# full_hand_circuit_esp_v7_1_no_butt.net
KiCad netlist of a schematic drawn in EAGLE
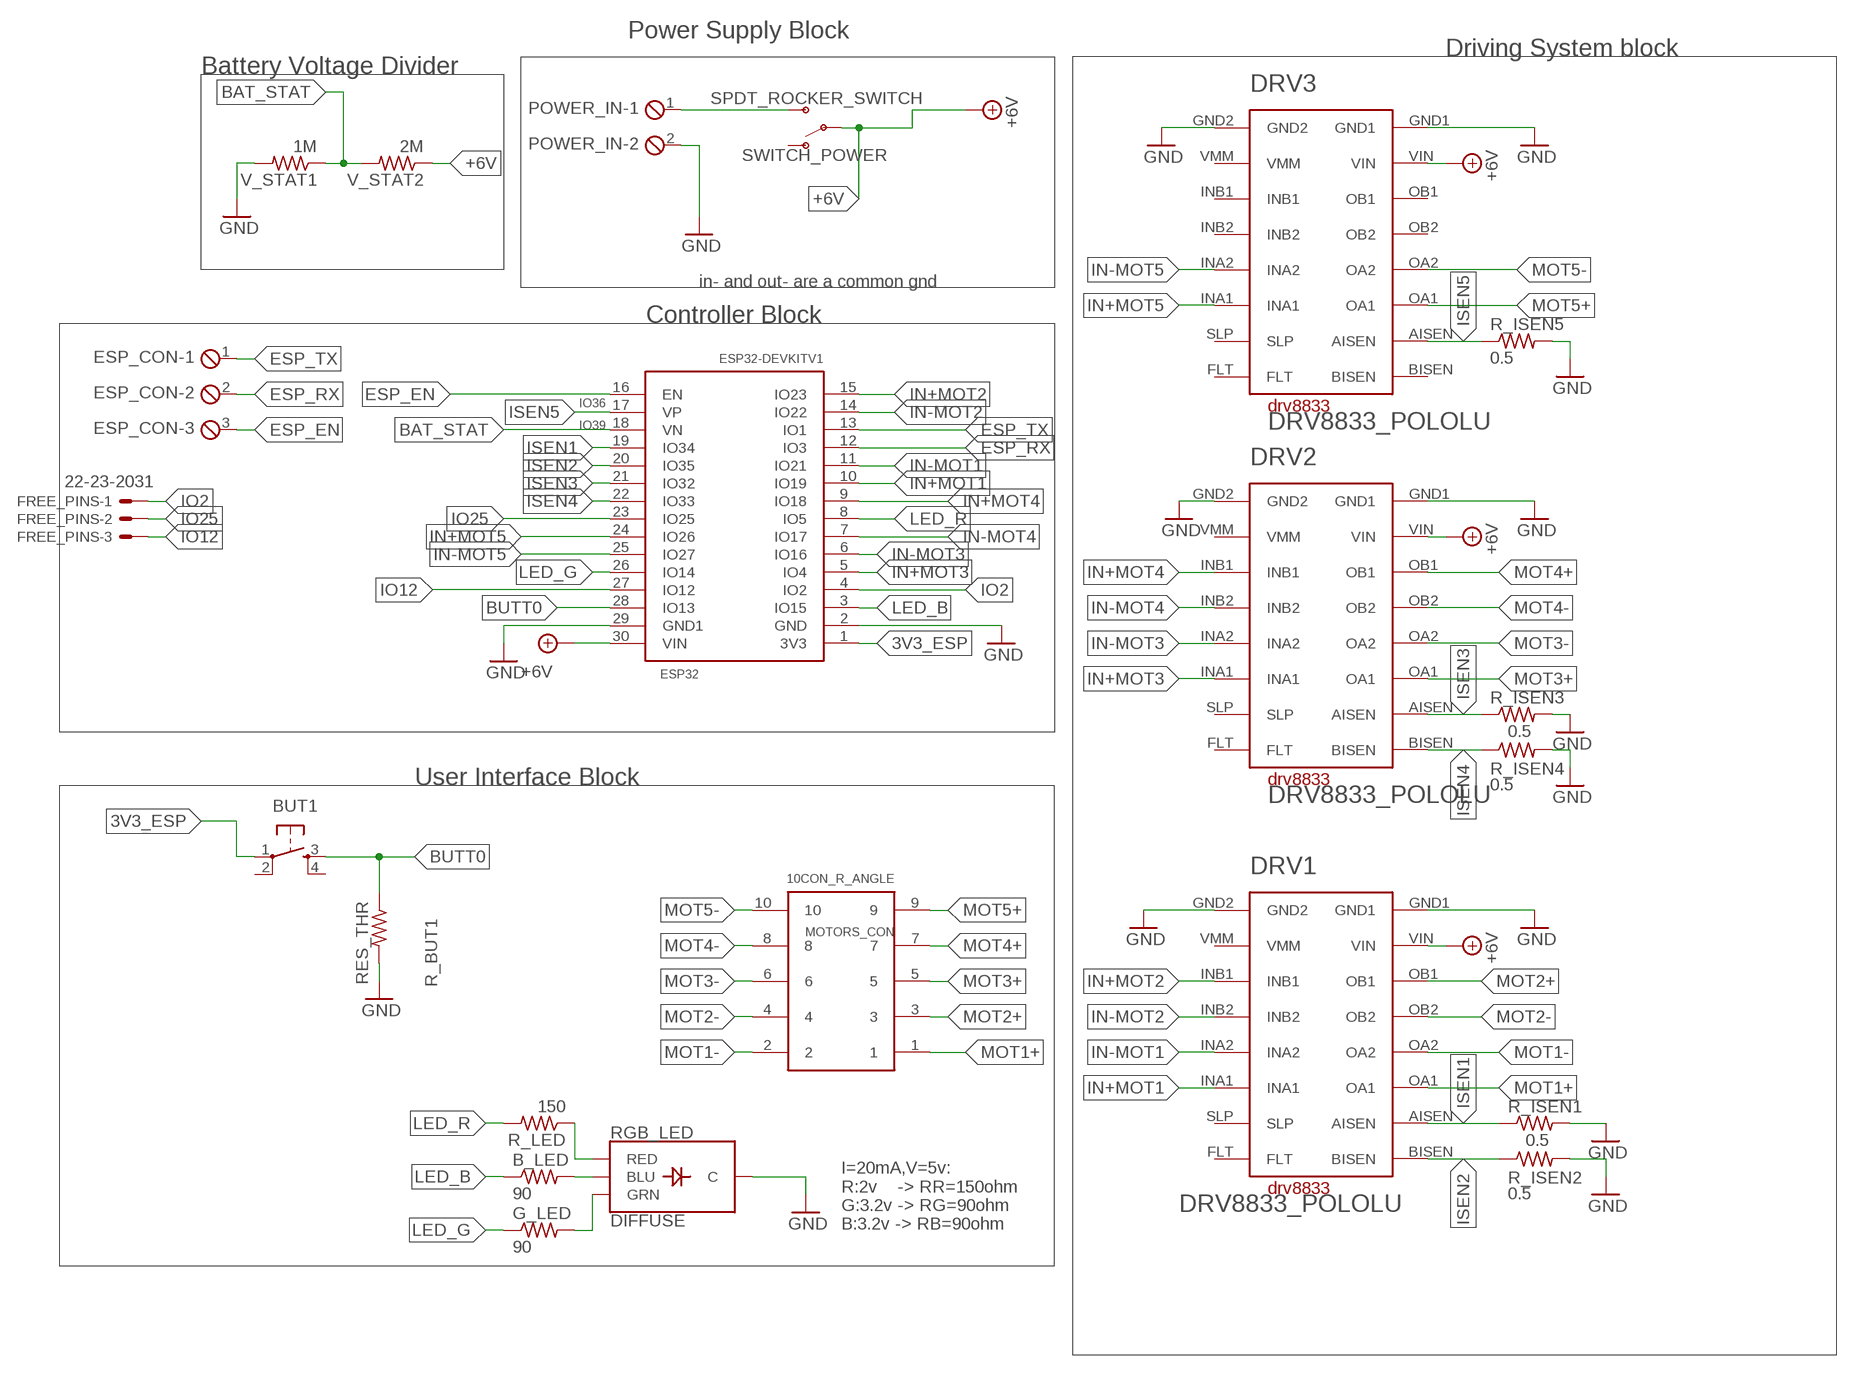
[diagram p0: schematic, sheet 1]

(export (version "E")
  (design (tool "Eeschema 10.0.6"))
  (components
    (comp (ref "BUT1")
      (value "PUSH_BUTTON")
      (footprint "eagle-import:B3F-40XX")
      (libsource (lib "eagle-import") (part "PUSH_BUTTON"))
    )
    (comp (ref "B_LED")
      (value "90")
      (footprint "eagle-import:R_THR")
      (libsource (lib "eagle-import") (part "RES_THR"))
    )
    (comp (ref "DRV1")
      (value "DRV8833_POLOLU")
      (footprint "eagle-import:DRV8833_POLOLU")
      (libsource (lib "eagle-import") (part "DRV8833_POLOLU"))
    )
    (comp (ref "DRV2")
      (value "DRV8833_POLOLU")
      (footprint "eagle-import:DRV8833_POLOLU")
      (libsource (lib "eagle-import") (part "DRV8833_POLOLU"))
    )
    (comp (ref "DRV3")
      (value "DRV8833_POLOLU")
      (footprint "eagle-import:DRV8833_POLOLU")
      (libsource (lib "eagle-import") (part "DRV8833_POLOLU"))
    )
    (comp (ref "ESP32")
      (value "ESP32DEVKITV1")
      (footprint "eagle-import:ESP32-DEVKITV1")
      (libsource (lib "eagle-import") (part "ESP32DEVKITV1"))
    )
    (comp (ref "ESP_CON")
      (value "MPT3")
      (footprint "eagle-import:3POL254")
      (libsource (lib "eagle-import") (part "MPT3"))
    )
    (comp (ref "FREE_PINS")
      (value "22-23-2031")
      (footprint "eagle-import:22-23-2031")
      (fields (field (name "MF") "MOLEX"))
      (libsource (lib "eagle-import") (part "22-23-2031"))
    )
    (comp (ref "G_LED")
      (value "90")
      (footprint "eagle-import:R_THR")
      (libsource (lib "eagle-import") (part "RES_THR"))
    )
    (comp (ref "MOTORS_CON")
      (value "10CON_R_ANGLE")
      (footprint "eagle-import:CON10_R_ANGLE")
      (libsource (lib "eagle-import") (part "10CON_R_ANGLE"))
    )
    (comp (ref "POWER_IN")
      (value "MPT2")
      (footprint "eagle-import:2POL254")
      (libsource (lib "eagle-import") (part "MPT2"))
    )
    (comp (ref "RGB_LED")
      (value "DIFFUSE")
      (footprint "eagle-import:LED-RGB-THRU")
      (libsource (lib "eagle-import") (part "LED_RGB_CC"))
    )
    (comp (ref "R_BUT1")
      (value "RES_THR")
      (footprint "eagle-import:R_THR")
      (libsource (lib "eagle-import") (part "RES_THR"))
    )
    (comp (ref "R_ISEN1")
      (value "0.5")
      (footprint "eagle-import:R_THR")
      (libsource (lib "eagle-import") (part "RES_THR"))
    )
    (comp (ref "R_ISEN2")
      (value "0.5")
      (footprint "eagle-import:R_THR")
      (libsource (lib "eagle-import") (part "RES_THR"))
    )
    (comp (ref "R_ISEN3")
      (value "0.5")
      (footprint "eagle-import:R_THR")
      (libsource (lib "eagle-import") (part "RES_THR"))
    )
    (comp (ref "R_ISEN4")
      (value "0.5")
      (footprint "eagle-import:R_THR")
      (libsource (lib "eagle-import") (part "RES_THR"))
    )
    (comp (ref "R_ISEN5")
      (value "0.5")
      (footprint "eagle-import:R_THR")
      (libsource (lib "eagle-import") (part "RES_THR"))
    )
    (comp (ref "R_LED")
      (value "150")
      (footprint "eagle-import:R_THR")
      (libsource (lib "eagle-import") (part "RES_THR"))
    )
    (comp (ref "SWITCH_POWER")
      (value "SPDT_ROCKER_SWITCH")
      (footprint "eagle-import:SWITCH_SPDT_PTH_11.6X4.0MM")
      (libsource (lib "eagle-import") (part "SPDT_ROCKER_SWITCH"))
    )
    (comp (ref "V_STAT1")
      (value "1M")
      (footprint "eagle-import:R_THR")
      (libsource (lib "eagle-import") (part "RES_THR"))
    )
    (comp (ref "V_STAT2")
      (value "2M")
      (footprint "eagle-import:R_THR")
      (libsource (lib "eagle-import") (part "RES_THR"))
    )
  )
  (nets
    (net (code "1") (name "+6V") (class "Default")
      (node (ref "DRV1") (pin "VIN") (pinfunction "VIN_VIN") (pintype "bidirectional"))
      (node (ref "DRV2") (pin "VIN") (pinfunction "VIN_VIN") (pintype "bidirectional"))
      (node (ref "DRV3") (pin "VIN") (pinfunction "VIN_VIN") (pintype "bidirectional"))
      (node (ref "ESP32") (pin "30") (pinfunction "VIN_30") (pintype "bidirectional"))
      (node (ref "SWITCH_POWER") (pin "2") (pinfunction "P_2") (pintype "passive"))
      (node (ref "V_STAT2") (pin "1") (pinfunction "1_1") (pintype "passive"))
    )
    (net (code "2") (name "3V3_ESP") (class "Default")
      (node (ref "BUT1") (pin "1") (pinfunction "P_1") (pintype "passive"))
      (node (ref "ESP32") (pin "1") (pinfunction "3V3_1") (pintype "bidirectional"))
    )
    (net (code "3") (name "BAT_STAT") (class "Default")
      (node (ref "ESP32") (pin "18") (pinfunction "VN_18") (pintype "bidirectional"))
      (node (ref "V_STAT1") (pin "1") (pinfunction "1_1") (pintype "passive"))
      (node (ref "V_STAT2") (pin "2") (pinfunction "2_2") (pintype "passive"))
    )
    (net (code "4") (name "BUTT0") (class "Default")
      (node (ref "BUT1") (pin "3") (pinfunction "S_3") (pintype "passive"))
      (node (ref "ESP32") (pin "28") (pinfunction "IO13_28") (pintype "bidirectional"))
      (node (ref "R_BUT1") (pin "1") (pinfunction "1_1") (pintype "passive"))
    )
    (net (code "5") (name "ESP_EN") (class "Default")
      (node (ref "ESP32") (pin "16") (pinfunction "EN_16") (pintype "bidirectional"))
      (node (ref "ESP_CON") (pin "3") (pinfunction "1_3") (pintype "passive"))
    )
    (net (code "6") (name "ESP_RX") (class "Default")
      (node (ref "ESP32") (pin "12") (pinfunction "IO3_12") (pintype "bidirectional"))
      (node (ref "ESP_CON") (pin "2") (pinfunction "1_2") (pintype "passive"))
    )
    (net (code "7") (name "ESP_TX") (class "Default")
      (node (ref "ESP32") (pin "13") (pinfunction "IO1_13") (pintype "bidirectional"))
      (node (ref "ESP_CON") (pin "1") (pinfunction "1_1") (pintype "passive"))
    )
    (net (code "8") (name "GND") (class "Default")
      (node (ref "DRV1") (pin "GND1") (pinfunction "GND1_GND1") (pintype "bidirectional"))
      (node (ref "DRV1") (pin "GND2") (pinfunction "GND2_GND2") (pintype "bidirectional"))
      (node (ref "DRV2") (pin "GND1") (pinfunction "GND1_GND1") (pintype "bidirectional"))
      (node (ref "DRV2") (pin "GND2") (pinfunction "GND2_GND2") (pintype "bidirectional"))
      (node (ref "DRV3") (pin "GND1") (pinfunction "GND1_GND1") (pintype "bidirectional"))
      (node (ref "DRV3") (pin "GND2") (pinfunction "GND2_GND2") (pintype "bidirectional"))
      (node (ref "ESP32") (pin "2") (pinfunction "GND_2") (pintype "bidirectional"))
      (node (ref "ESP32") (pin "29") (pinfunction "GND1_29") (pintype "bidirectional"))
      (node (ref "POWER_IN") (pin "2") (pinfunction "1_2") (pintype "passive"))
      (node (ref "RGB_LED") (pin "2") (pinfunction "C_2") (pintype "bidirectional"))
      (node (ref "R_BUT1") (pin "2") (pinfunction "2_2") (pintype "passive"))
      (node (ref "R_ISEN1") (pin "2") (pinfunction "2_2") (pintype "passive"))
      (node (ref "R_ISEN2") (pin "2") (pinfunction "2_2") (pintype "passive"))
      (node (ref "R_ISEN3") (pin "2") (pinfunction "2_2") (pintype "passive"))
      (node (ref "R_ISEN4") (pin "2") (pinfunction "2_2") (pintype "passive"))
      (node (ref "R_ISEN5") (pin "2") (pinfunction "2_2") (pintype "passive"))
      (node (ref "V_STAT1") (pin "2") (pinfunction "2_2") (pintype "passive"))
    )
    (net (code "9") (name "IN+MOT1") (class "Default")
      (node (ref "DRV1") (pin "INA1") (pinfunction "INA1_INA1") (pintype "bidirectional"))
      (node (ref "ESP32") (pin "10") (pinfunction "IO19_10") (pintype "bidirectional"))
    )
    (net (code "10") (name "IN+MOT2") (class "Default")
      (node (ref "DRV1") (pin "INB1") (pinfunction "INB1_INB1") (pintype "bidirectional"))
      (node (ref "ESP32") (pin "15") (pinfunction "IO23_15") (pintype "bidirectional"))
    )
    (net (code "11") (name "IN+MOT3") (class "Default")
      (node (ref "DRV2") (pin "INA1") (pinfunction "INA1_INA1") (pintype "bidirectional"))
      (node (ref "ESP32") (pin "5") (pinfunction "IO4_5") (pintype "bidirectional"))
    )
    (net (code "12") (name "IN+MOT4") (class "Default")
      (node (ref "DRV2") (pin "INB1") (pinfunction "INB1_INB1") (pintype "bidirectional"))
      (node (ref "ESP32") (pin "9") (pinfunction "IO18_9") (pintype "bidirectional"))
    )
    (net (code "13") (name "IN+MOT5") (class "Default")
      (node (ref "DRV3") (pin "INA1") (pinfunction "INA1_INA1") (pintype "bidirectional"))
      (node (ref "ESP32") (pin "24") (pinfunction "IO26_24") (pintype "bidirectional"))
    )
    (net (code "14") (name "IN-MOT1") (class "Default")
      (node (ref "DRV1") (pin "INA2") (pinfunction "INA2_INA2") (pintype "bidirectional"))
      (node (ref "ESP32") (pin "11") (pinfunction "IO21_11") (pintype "bidirectional"))
    )
    (net (code "15") (name "IN-MOT2") (class "Default")
      (node (ref "DRV1") (pin "INB2") (pinfunction "INB2_INB2") (pintype "bidirectional"))
      (node (ref "ESP32") (pin "14") (pinfunction "IO22_14") (pintype "bidirectional"))
    )
    (net (code "16") (name "IN-MOT3") (class "Default")
      (node (ref "DRV2") (pin "INA2") (pinfunction "INA2_INA2") (pintype "bidirectional"))
      (node (ref "ESP32") (pin "6") (pinfunction "IO16_6") (pintype "bidirectional"))
    )
    (net (code "17") (name "IN-MOT4") (class "Default")
      (node (ref "DRV2") (pin "INB2") (pinfunction "INB2_INB2") (pintype "bidirectional"))
      (node (ref "ESP32") (pin "7") (pinfunction "IO17_7") (pintype "bidirectional"))
    )
    (net (code "18") (name "IN-MOT5") (class "Default")
      (node (ref "DRV3") (pin "INA2") (pinfunction "INA2_INA2") (pintype "bidirectional"))
      (node (ref "ESP32") (pin "25") (pinfunction "IO27_25") (pintype "bidirectional"))
    )
    (net (code "19") (name "IO2") (class "Default")
      (node (ref "ESP32") (pin "4") (pinfunction "IO2_4") (pintype "bidirectional"))
      (node (ref "FREE_PINS") (pin "1") (pinfunction "S_1") (pintype "passive"))
    )
    (net (code "20") (name "IO12") (class "Default")
      (node (ref "ESP32") (pin "27") (pinfunction "IO12_27") (pintype "bidirectional"))
      (node (ref "FREE_PINS") (pin "3") (pinfunction "S_3") (pintype "passive"))
    )
    (net (code "21") (name "IO25") (class "Default")
      (node (ref "ESP32") (pin "23") (pinfunction "IO25_23") (pintype "bidirectional"))
      (node (ref "FREE_PINS") (pin "2") (pinfunction "S_2") (pintype "passive"))
    )
    (net (code "22") (name "ISEN1") (class "Default")
      (node (ref "DRV1") (pin "AISEN") (pinfunction "AISEN_AISEN") (pintype "bidirectional"))
      (node (ref "ESP32") (pin "19") (pinfunction "IO34_19") (pintype "bidirectional"))
      (node (ref "R_ISEN1") (pin "1") (pinfunction "1_1") (pintype "passive"))
    )
    (net (code "23") (name "ISEN2") (class "Default")
      (node (ref "DRV1") (pin "BISEN") (pinfunction "BISEN_BISEN") (pintype "bidirectional"))
      (node (ref "ESP32") (pin "20") (pinfunction "IO35_20") (pintype "bidirectional"))
      (node (ref "R_ISEN2") (pin "1") (pinfunction "1_1") (pintype "passive"))
    )
    (net (code "24") (name "ISEN3") (class "Default")
      (node (ref "DRV2") (pin "AISEN") (pinfunction "AISEN_AISEN") (pintype "bidirectional"))
      (node (ref "ESP32") (pin "21") (pinfunction "IO32_21") (pintype "bidirectional"))
      (node (ref "R_ISEN3") (pin "1") (pinfunction "1_1") (pintype "passive"))
    )
    (net (code "25") (name "ISEN4") (class "Default")
      (node (ref "DRV2") (pin "BISEN") (pinfunction "BISEN_BISEN") (pintype "bidirectional"))
      (node (ref "ESP32") (pin "22") (pinfunction "IO33_22") (pintype "bidirectional"))
      (node (ref "R_ISEN4") (pin "1") (pinfunction "1_1") (pintype "passive"))
    )
    (net (code "26") (name "ISEN5") (class "Default")
      (node (ref "DRV3") (pin "AISEN") (pinfunction "AISEN_AISEN") (pintype "bidirectional"))
      (node (ref "ESP32") (pin "17") (pinfunction "VP_17") (pintype "bidirectional"))
      (node (ref "R_ISEN5") (pin "1") (pinfunction "1_1") (pintype "passive"))
    )
    (net (code "27") (name "LED_B") (class "Default")
      (node (ref "B_LED") (pin "1") (pinfunction "1_1") (pintype "passive"))
      (node (ref "ESP32") (pin "3") (pinfunction "IO15_3") (pintype "bidirectional"))
    )
    (net (code "28") (name "LED_G") (class "Default")
      (node (ref "ESP32") (pin "26") (pinfunction "IO14_26") (pintype "bidirectional"))
      (node (ref "G_LED") (pin "1") (pinfunction "1_1") (pintype "passive"))
    )
    (net (code "29") (name "LED_R") (class "Default")
      (node (ref "ESP32") (pin "8") (pinfunction "IO5_8") (pintype "bidirectional"))
      (node (ref "R_LED") (pin "2") (pinfunction "2_2") (pintype "passive"))
    )
    (net (code "30") (name "MOT1+") (class "Default")
      (node (ref "DRV1") (pin "OA1") (pinfunction "OA1_OA1") (pintype "bidirectional"))
      (node (ref "MOTORS_CON") (pin "1") (pinfunction "1_1") (pintype "bidirectional"))
    )
    (net (code "31") (name "MOT1-") (class "Default")
      (node (ref "DRV1") (pin "OA2") (pinfunction "OA2_OA2") (pintype "bidirectional"))
      (node (ref "MOTORS_CON") (pin "2") (pinfunction "2_2") (pintype "bidirectional"))
    )
    (net (code "32") (name "MOT2+") (class "Default")
      (node (ref "DRV1") (pin "OB1") (pinfunction "OB1_OB1") (pintype "bidirectional"))
      (node (ref "MOTORS_CON") (pin "3") (pinfunction "3_3") (pintype "bidirectional"))
    )
    (net (code "33") (name "MOT2-") (class "Default")
      (node (ref "DRV1") (pin "OB2") (pinfunction "OB2_OB2") (pintype "bidirectional"))
      (node (ref "MOTORS_CON") (pin "4") (pinfunction "4_4") (pintype "bidirectional"))
    )
    (net (code "34") (name "MOT3+") (class "Default")
      (node (ref "DRV2") (pin "OA1") (pinfunction "OA1_OA1") (pintype "bidirectional"))
      (node (ref "MOTORS_CON") (pin "5") (pinfunction "5_5") (pintype "bidirectional"))
    )
    (net (code "35") (name "MOT3-") (class "Default")
      (node (ref "DRV2") (pin "OA2") (pinfunction "OA2_OA2") (pintype "bidirectional"))
      (node (ref "MOTORS_CON") (pin "6") (pinfunction "6_6") (pintype "bidirectional"))
    )
    (net (code "36") (name "MOT4+") (class "Default")
      (node (ref "DRV2") (pin "OB1") (pinfunction "OB1_OB1") (pintype "bidirectional"))
      (node (ref "MOTORS_CON") (pin "7") (pinfunction "7_7") (pintype "bidirectional"))
    )
    (net (code "37") (name "MOT4-") (class "Default")
      (node (ref "DRV2") (pin "OB2") (pinfunction "OB2_OB2") (pintype "bidirectional"))
      (node (ref "MOTORS_CON") (pin "8") (pinfunction "8_8") (pintype "bidirectional"))
    )
    (net (code "38") (name "MOT5+") (class "Default")
      (node (ref "DRV3") (pin "OA1") (pinfunction "OA1_OA1") (pintype "bidirectional"))
      (node (ref "MOTORS_CON") (pin "9") (pinfunction "9_9") (pintype "bidirectional"))
    )
    (net (code "39") (name "MOT5-") (class "Default")
      (node (ref "DRV3") (pin "OA2") (pinfunction "OA2_OA2") (pintype "bidirectional"))
      (node (ref "MOTORS_CON") (pin "10") (pinfunction "10_10") (pintype "bidirectional"))
    )
    (net (code "40") (name "Net-(RGB_LED-BLU)") (class "Default")
      (node (ref "B_LED") (pin "2") (pinfunction "2_2") (pintype "passive"))
      (node (ref "RGB_LED") (pin "4") (pinfunction "BLU_4") (pintype "bidirectional"))
    )
    (net (code "41") (name "Net-(RGB_LED-GRN)") (class "Default")
      (node (ref "G_LED") (pin "2") (pinfunction "2_2") (pintype "passive"))
      (node (ref "RGB_LED") (pin "3") (pinfunction "GRN_3") (pintype "bidirectional"))
    )
    (net (code "42") (name "Net-(RGB_LED-RED)") (class "Default")
      (node (ref "RGB_LED") (pin "1") (pinfunction "RED_1") (pintype "bidirectional"))
      (node (ref "R_LED") (pin "1") (pinfunction "1_1") (pintype "passive"))
    )
    (net (code "43") (name "Net-(SWITCH_POWER-S)") (class "Default")
      (node (ref "POWER_IN") (pin "1") (pinfunction "1_1") (pintype "passive"))
      (node (ref "SWITCH_POWER") (pin "3") (pinfunction "S_3") (pintype "passive"))
    )
    (net (code "44") (name "unconnected-(BUT1-P1-Pad2)") (class "Default")
      (node (ref "BUT1") (pin "2") (pinfunction "P1_2") (pintype "passive"))
    )
    (net (code "45") (name "unconnected-(BUT1-S1-Pad4)") (class "Default")
      (node (ref "BUT1") (pin "4") (pinfunction "S1_4") (pintype "passive"))
    )
    (net (code "46") (name "unconnected-(DRV1-PadFLT)") (class "Default")
      (node (ref "DRV1") (pin "FLT") (pinfunction "FLT_FLT") (pintype "bidirectional"))
    )
    (net (code "47") (name "unconnected-(DRV1-PadSLP)") (class "Default")
      (node (ref "DRV1") (pin "SLP") (pinfunction "SLP_SLP") (pintype "bidirectional"))
    )
    (net (code "48") (name "unconnected-(DRV1-PadVMM)") (class "Default")
      (node (ref "DRV1") (pin "VMM") (pinfunction "VMM_VMM") (pintype "output"))
    )
    (net (code "49") (name "unconnected-(DRV2-PadFLT)") (class "Default")
      (node (ref "DRV2") (pin "FLT") (pinfunction "FLT_FLT") (pintype "bidirectional"))
    )
    (net (code "50") (name "unconnected-(DRV2-PadSLP)") (class "Default")
      (node (ref "DRV2") (pin "SLP") (pinfunction "SLP_SLP") (pintype "bidirectional"))
    )
    (net (code "51") (name "unconnected-(DRV2-PadVMM)") (class "Default")
      (node (ref "DRV2") (pin "VMM") (pinfunction "VMM_VMM") (pintype "output"))
    )
    (net (code "52") (name "unconnected-(DRV3-PadBISEN)") (class "Default")
      (node (ref "DRV3") (pin "BISEN") (pinfunction "BISEN_BISEN") (pintype "bidirectional"))
    )
    (net (code "53") (name "unconnected-(DRV3-PadFLT)") (class "Default")
      (node (ref "DRV3") (pin "FLT") (pinfunction "FLT_FLT") (pintype "bidirectional"))
    )
    (net (code "54") (name "unconnected-(DRV3-PadINB1)") (class "Default")
      (node (ref "DRV3") (pin "INB1") (pinfunction "INB1_INB1") (pintype "bidirectional"))
    )
    (net (code "55") (name "unconnected-(DRV3-PadINB2)") (class "Default")
      (node (ref "DRV3") (pin "INB2") (pinfunction "INB2_INB2") (pintype "bidirectional"))
    )
    (net (code "56") (name "unconnected-(DRV3-PadOB1)") (class "Default")
      (node (ref "DRV3") (pin "OB1") (pinfunction "OB1_OB1") (pintype "bidirectional"))
    )
    (net (code "57") (name "unconnected-(DRV3-PadOB2)") (class "Default")
      (node (ref "DRV3") (pin "OB2") (pinfunction "OB2_OB2") (pintype "bidirectional"))
    )
    (net (code "58") (name "unconnected-(DRV3-PadSLP)") (class "Default")
      (node (ref "DRV3") (pin "SLP") (pinfunction "SLP_SLP") (pintype "bidirectional"))
    )
    (net (code "59") (name "unconnected-(DRV3-PadVMM)") (class "Default")
      (node (ref "DRV3") (pin "VMM") (pinfunction "VMM_VMM") (pintype "output"))
    )
    (net (code "60") (name "unconnected-(SWITCH_POWER-O-Pad1)") (class "Default")
      (node (ref "SWITCH_POWER") (pin "1") (pinfunction "O_1") (pintype "passive"))
    )
  )
)
